# NanoV33.net
KiCad netlist of a schematic drawn in EAGLE
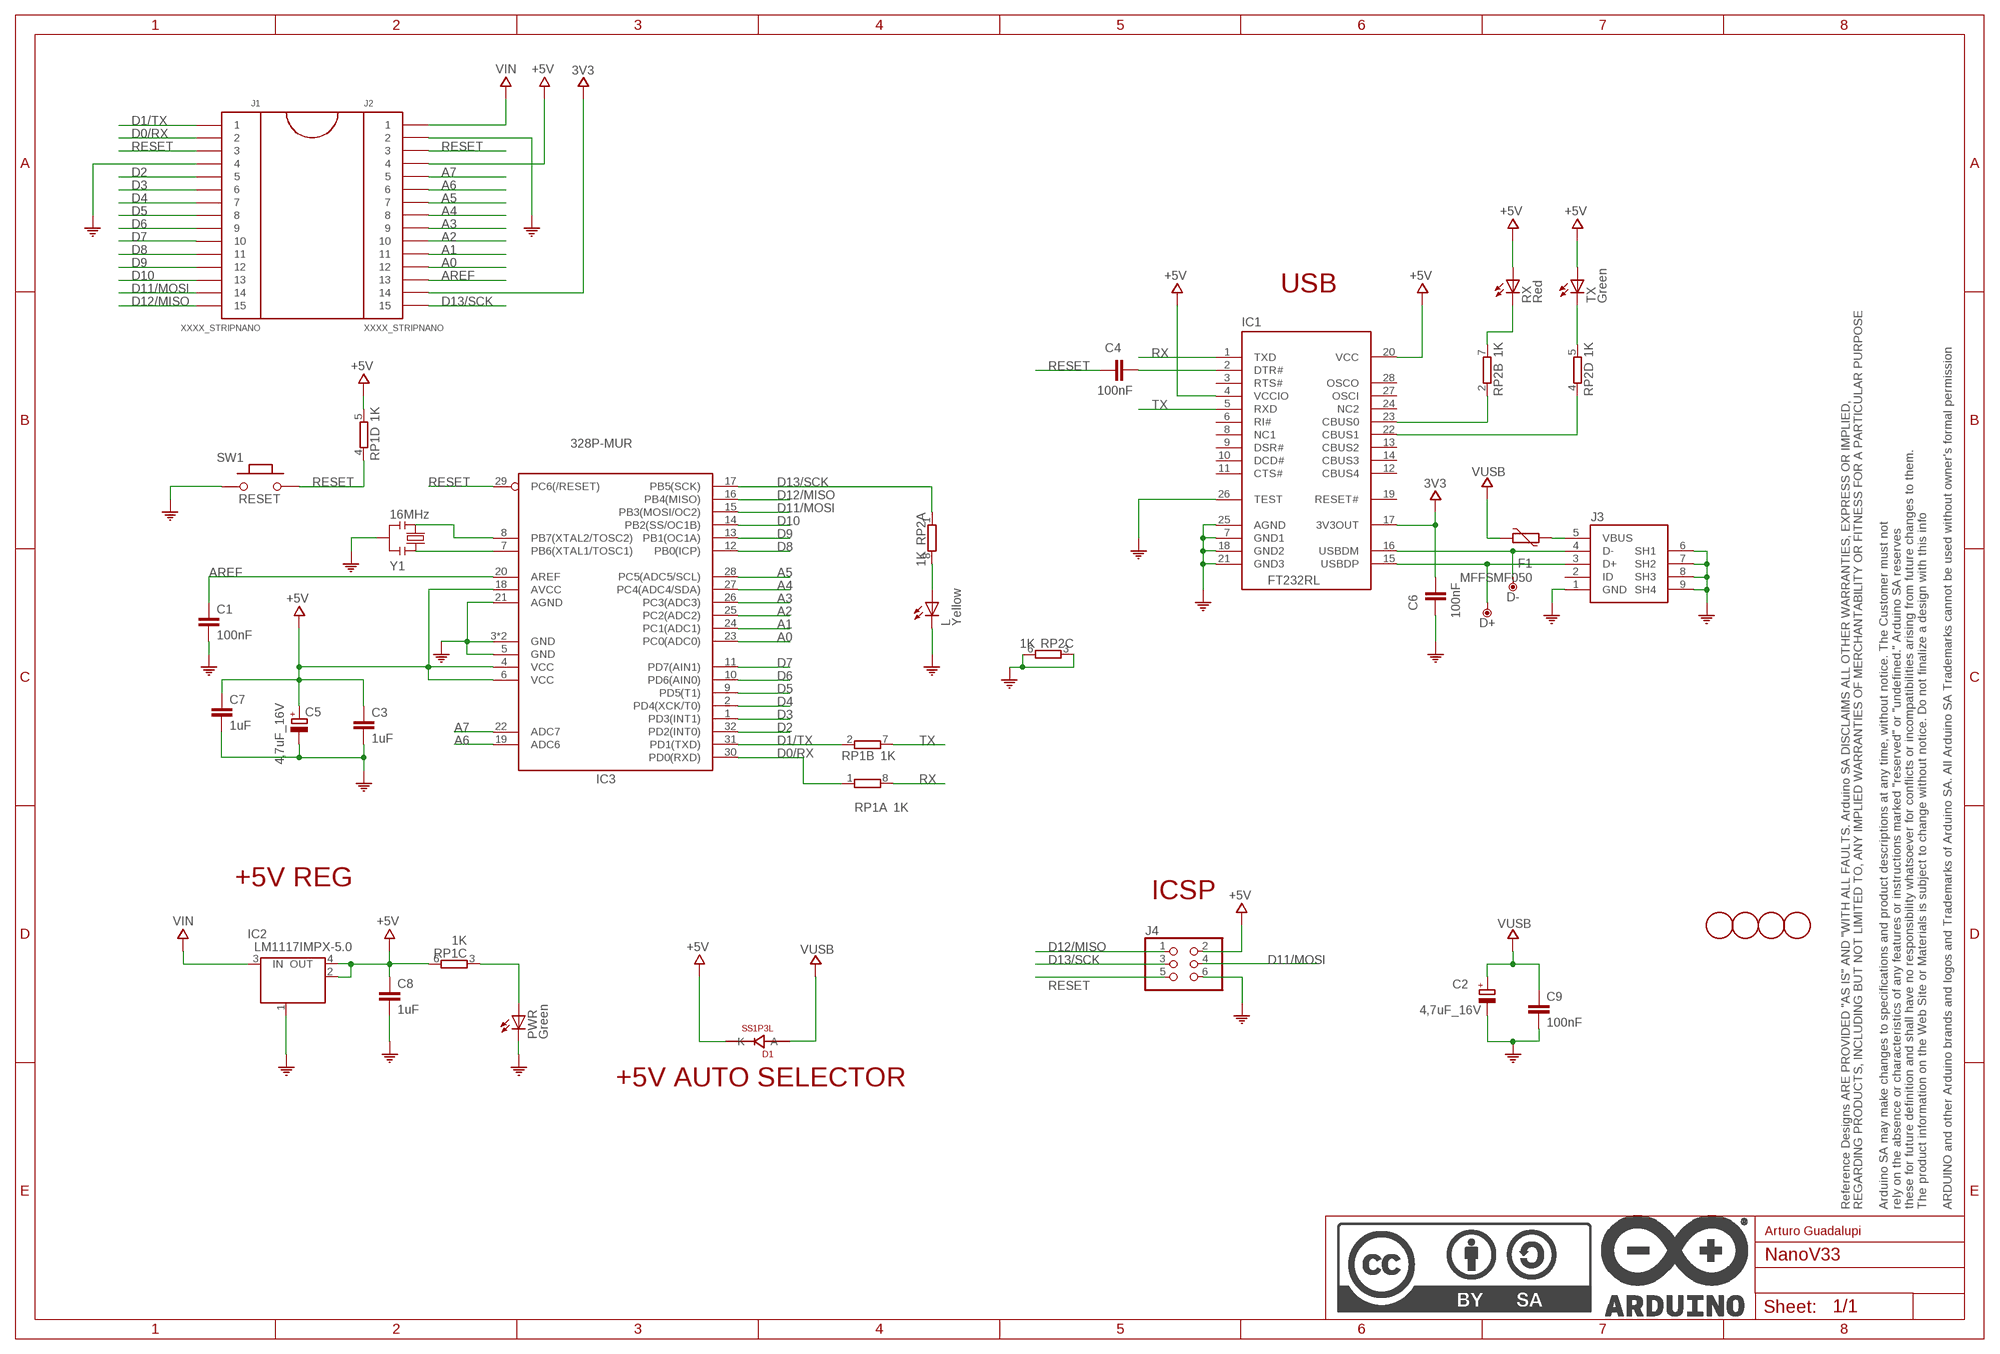
[diagram p0: schematic, sheet 1]

(export (version "E")
  (design (tool "Eeschema 10.0.6"))
  (components
    (comp (ref "C1")
      (value "100nF")
      (footprint "eagle-import:C0603-ROUND")
      (fields (field (name "PART_NUMBER") "cl10b104kbnc"))
      (libsource (lib "eagle-import") (part "0015_100NF_0603"))
    )
    (comp (ref "C2")
      (value "4,7uF_16V")
      (footprint "eagle-import:TAN-A")
      (fields (field (name "PART_NUMBER") "TAJA475MO16RNJ"))
      (libsource (lib "eagle-import") (part "0833_TAJA475MO16RNJ"))
    )
    (comp (ref "C3")
      (value "1uF")
      (footprint "eagle-import:C0603-ROUND")
      (fields (field (name "PART_NUMBER") "1uF_0603/GRM188R61E105KA12D"))
      (libsource (lib "eagle-import") (part "0006_1UF_0603/GRM188R61E105KA12D"))
    )
    (comp (ref "C4")
      (value "100nF")
      (footprint "eagle-import:C0603-ROUND")
      (fields (field (name "PART_NUMBER") "cl10b104kbnc"))
      (libsource (lib "eagle-import") (part "0015_100NF_0603"))
    )
    (comp (ref "C5")
      (value "4,7uF_16V")
      (footprint "eagle-import:TAN-A")
      (fields (field (name "PART_NUMBER") "TAJA475MO16RNJ"))
      (libsource (lib "eagle-import") (part "0833_TAJA475MO16RNJ"))
    )
    (comp (ref "C6")
      (value "100nF")
      (footprint "eagle-import:C0603-ROUND")
      (fields (field (name "PART_NUMBER") "cl10b104kbnc"))
      (libsource (lib "eagle-import") (part "0015_100NF_0603"))
    )
    (comp (ref "C7")
      (value "1uF")
      (footprint "eagle-import:C0603-ROUND")
      (fields (field (name "PART_NUMBER") "1uF_0603/GRM188R61E105KA12D"))
      (libsource (lib "eagle-import") (part "0006_1UF_0603/GRM188R61E105KA12D"))
    )
    (comp (ref "C8")
      (value "1uF")
      (footprint "eagle-import:C0603-ROUND")
      (fields (field (name "PART_NUMBER") "1uF_0603/GRM188R61E105KA12D"))
      (libsource (lib "eagle-import") (part "0006_1UF_0603/GRM188R61E105KA12D"))
    )
    (comp (ref "C9")
      (value "100nF")
      (footprint "eagle-import:C0603-ROUND")
      (fields (field (name "PART_NUMBER") "cl10b104kbnc"))
      (libsource (lib "eagle-import") (part "0015_100NF_0603"))
    )
    (comp (ref "D+")
      (value "DNP")
      (footprint "eagle-import:TP-1.00MM")
      (libsource (lib "eagle-import") (part "TPTP-1.00MM"))
    )
    (comp (ref "D-")
      (value "DNP")
      (footprint "eagle-import:TP-1.00MM")
      (libsource (lib "eagle-import") (part "TPTP-1.00MM"))
    )
    (comp (ref "D1")
      (value "SS1P3L")
      (footprint "eagle-import:DO220AAL")
      (fields (field (name "PART_NUMBER") "SS1P3L-M3/84A"))
      (libsource (lib "eagle-import") (part "0025_SS1P3L-M3/84A"))
    )
    (comp (ref "F1")
      (value "MFFSMF050")
      (footprint "eagle-import:0603-1608X90N")
      (fields (field (name "MANUFACTURER") "Bourns Inc "))
      (libsource (lib "eagle-import") (part "PTC"))
    )
    (comp (ref "FRAME1")
      (value "DNP")
      (footprint "eagle-import:FRAME")
      (libsource (lib "eagle-import") (part "A3-FRAME"))
    )
    (comp (ref "IC1")
      (value "FT232RL")
      (footprint "eagle-import:SSOP28")
      (libsource (lib "eagle-import") (part "0226_FT232RL"))
    )
    (comp (ref "IC2")
      (value "LM1117IMPX-5.0")
      (footprint "eagle-import:LINEAR_SOT223")
      (libsource (lib "eagle-import") (part "0022_LM1117IMPX-5.0"))
    )
    (comp (ref "IC3")
      (value "328P-MUR")
      (footprint "eagle-import:VQFN32")
      (fields (field (name "MANUFACTURER") "ATMEL"))
      (libsource (lib "eagle-import") (part "ATMEGA328P-32MUR"))
    )
    (comp (ref "J1")
      (value "XXXX_STRIPNANO")
      (footprint "eagle-import:HEAD15-NOSS")
      (libsource (lib "eagle-import") (part "XXXX_STRIPNANO"))
    )
    (comp (ref "J2")
      (value "XXXX_STRIPNANO")
      (footprint "eagle-import:HEAD15-NOSS")
      (libsource (lib "eagle-import") (part "XXXX_STRIPNANO"))
    )
    (comp (ref "J3")
      (value "0219_14850")
      (footprint "eagle-import:USB-MINI-B_2")
      (fields (field (name "PART_NUMBER") "14850"))
      (libsource (lib "eagle-import") (part "0219_14850"))
    )
    (comp (ref "J4")
      (value "0114_PH254-203DF118A00V")
      (footprint "eagle-import:2X03")
      (fields (field (name "PART_NUMBER") "PH254-203DF118A00V"))
      (libsource (lib "eagle-import") (part "0114_PH254-203DF118A00V"))
    )
    (comp (ref "L")
      (value "Yellow")
      (footprint "eagle-import:CHIPLED_0805")
      (fields (field (name "PART_NUMBER") "KPT-2012YC"))
      (libsource (lib "eagle-import") (part "0044_KPT-2012YC"))
    )
    (comp (ref "PWR")
      (value "Green")
      (footprint "eagle-import:CHIPLED_0805")
      (fields (field (name "PART_NUMBER") "KPT-2012SGC"))
      (libsource (lib "eagle-import") (part "0043_KPT-2012SGC"))
    )
    (comp (ref "RP1")
      (value "1K")
      (footprint "eagle-import:CAY16")
      (fields (field (name "PART_NUMBER") "064R_1K_/_CAY16-102J4LF"))
      (libsource (lib "eagle-import") (part "0005_064R_1K_/_CAY16-102J4LF"))
    )
    (comp (ref "RP2")
      (value "1K")
      (footprint "eagle-import:CAY16")
      (fields (field (name "PART_NUMBER") "064R_1K_/_CAY16-102J4LF"))
      (libsource (lib "eagle-import") (part "0005_064R_1K_/_CAY16-102J4LF"))
    )
    (comp (ref "RX")
      (value "Red")
      (footprint "eagle-import:CHIPLED_0805")
      (fields (field (name "PART_NUMBER") "KTP-2012SURCK"))
      (libsource (lib "eagle-import") (part "0181_KTP-2012SURCK"))
    )
    (comp (ref "SW1")
      (value "RESET")
      (footprint "eagle-import:SMD_157SW")
      (fields (field (name "PART_NUMBER") "IT-1185AP1C-160G-G_T&R"))
      (libsource (lib "eagle-import") (part "0173_IT-1185AP1C-160G-G_T&R"))
    )
    (comp (ref "TX")
      (value "Green")
      (footprint "eagle-import:CHIPLED_0805")
      (fields (field (name "PART_NUMBER") "KPT-2012SGC"))
      (libsource (lib "eagle-import") (part "0043_KPT-2012SGC"))
    )
    (comp (ref "U$4")
      (value "DNP")
      (footprint "eagle-import:FD-1-1.5")
      (libsource (lib "eagle-import") (part "FIDUCIAL-1.5MM"))
    )
    (comp (ref "U$5")
      (value "DNP")
      (footprint "eagle-import:FD-1-1.5")
      (libsource (lib "eagle-import") (part "FIDUCIAL-1.5MM"))
    )
    (comp (ref "U$53")
      (value "DNP")
      (footprint "eagle-import:FD-1-1.5")
      (libsource (lib "eagle-import") (part "FIDUCIAL-1.5MM"))
    )
    (comp (ref "U$54")
      (value "DNP")
      (footprint "eagle-import:FD-1-1.5")
      (libsource (lib "eagle-import") (part "FIDUCIAL-1.5MM"))
    )
    (comp (ref "Y1")
      (value "16MHz")
      (footprint "eagle-import:RESONATOR")
      (fields (field (name "PART_NUMBER") "CSTCE16M0V53-R0"))
      (libsource (lib "eagle-import") (part "0011_CSTCE16M0V53-R0"))
    )
  )
  (nets
    (net (code "1") (name "+5V") (class "Default")
      (node (ref "C3") (pin "1") (pinfunction "1_1") (pintype "passive"))
      (node (ref "C5") (pin "1") (pinfunction "+_1") (pintype "passive"))
      (node (ref "C7") (pin "1") (pinfunction "1_1") (pintype "passive"))
      (node (ref "C8") (pin "1") (pinfunction "1_1") (pintype "passive"))
      (node (ref "D1") (pin "P$1") (pinfunction "K_P$1") (pintype "bidirectional"))
      (node (ref "IC1") (pin "20") (pinfunction "VCC_20") (pintype "power_in"))
      (node (ref "IC1") (pin "4") (pinfunction "VCCIO_4") (pintype "power_in"))
      (node (ref "IC2") (pin "2") (pinfunction "OUT_2") (pintype "passive"))
      (node (ref "IC2") (pin "4") (pinfunction "OUT_4") (pintype "passive"))
      (node (ref "IC3") (pin "18") (pinfunction "AVCC_18") (pintype "bidirectional"))
      (node (ref "IC3") (pin "4") (pinfunction "VCC_4") (pintype "bidirectional"))
      (node (ref "IC3") (pin "6") (pinfunction "VCC_6") (pintype "bidirectional"))
      (node (ref "J2") (pin "4") (pinfunction "4_4") (pintype "passive"))
      (node (ref "J4") (pin "2") (pinfunction "2_2") (pintype "passive"))
      (node (ref "RP1") (pin "5") (pinfunction "2_5") (pintype "passive"))
      (node (ref "RP1") (pin "6") (pinfunction "2_6") (pintype "passive"))
      (node (ref "RX") (pin "A") (pinfunction "A_A") (pintype "passive"))
      (node (ref "TX") (pin "A") (pinfunction "A_A") (pintype "passive"))
    )
    (net (code "2") (name "/A0") (class "Default")
      (node (ref "IC3") (pin "23") (pinfunction "PC0(ADC0)_23") (pintype "bidirectional"))
      (node (ref "J2") (pin "12") (pinfunction "12_12") (pintype "passive"))
    )
    (net (code "3") (name "/A1") (class "Default")
      (node (ref "IC3") (pin "24") (pinfunction "PC1(ADC1)_24") (pintype "bidirectional"))
      (node (ref "J2") (pin "11") (pinfunction "11_11") (pintype "passive"))
    )
    (net (code "4") (name "/A2") (class "Default")
      (node (ref "IC3") (pin "25") (pinfunction "PC2(ADC2)_25") (pintype "bidirectional"))
      (node (ref "J2") (pin "10") (pinfunction "10_10") (pintype "passive"))
    )
    (net (code "5") (name "/A3") (class "Default")
      (node (ref "IC3") (pin "26") (pinfunction "PC3(ADC3)_26") (pintype "bidirectional"))
      (node (ref "J2") (pin "9") (pinfunction "9_9") (pintype "passive"))
    )
    (net (code "6") (name "/A4") (class "Default")
      (node (ref "IC3") (pin "27") (pinfunction "PC4(ADC4/SDA)_27") (pintype "bidirectional"))
      (node (ref "J2") (pin "8") (pinfunction "8_8") (pintype "passive"))
    )
    (net (code "7") (name "/A5") (class "Default")
      (node (ref "IC3") (pin "28") (pinfunction "PC5(ADC5/SCL)_28") (pintype "bidirectional"))
      (node (ref "J2") (pin "7") (pinfunction "7_7") (pintype "passive"))
    )
    (net (code "8") (name "/A6") (class "Default")
      (node (ref "IC3") (pin "19") (pinfunction "ADC6_19") (pintype "bidirectional"))
      (node (ref "J2") (pin "6") (pinfunction "6_6") (pintype "passive"))
    )
    (net (code "9") (name "/A7") (class "Default")
      (node (ref "IC3") (pin "22") (pinfunction "ADC7_22") (pintype "bidirectional"))
      (node (ref "J2") (pin "5") (pinfunction "5_5") (pintype "passive"))
    )
    (net (code "10") (name "/AREF") (class "Default")
      (node (ref "C1") (pin "1") (pinfunction "1_1") (pintype "passive"))
      (node (ref "IC3") (pin "20") (pinfunction "AREF_20") (pintype "bidirectional"))
      (node (ref "J2") (pin "13") (pinfunction "13_13") (pintype "passive"))
    )
    (net (code "11") (name "/D0{slash}RX") (class "Default")
      (node (ref "IC3") (pin "30") (pinfunction "PD0(RXD)_30") (pintype "bidirectional"))
      (node (ref "J1") (pin "2") (pinfunction "2_2") (pintype "passive"))
      (node (ref "RP1") (pin "1") (pinfunction "1_1") (pintype "passive"))
    )
    (net (code "12") (name "/D1{slash}TX") (class "Default")
      (node (ref "IC3") (pin "31") (pinfunction "PD1(TXD)_31") (pintype "bidirectional"))
      (node (ref "J1") (pin "1") (pinfunction "1_1") (pintype "passive"))
      (node (ref "RP1") (pin "2") (pinfunction "1_2") (pintype "passive"))
    )
    (net (code "13") (name "/D2") (class "Default")
      (node (ref "IC3") (pin "32") (pinfunction "PD2(INT0)_32") (pintype "bidirectional"))
      (node (ref "J1") (pin "5") (pinfunction "5_5") (pintype "passive"))
    )
    (net (code "14") (name "/D3") (class "Default")
      (node (ref "IC3") (pin "1") (pinfunction "PD3(INT1)_1") (pintype "bidirectional"))
      (node (ref "J1") (pin "6") (pinfunction "6_6") (pintype "passive"))
    )
    (net (code "15") (name "/D4") (class "Default")
      (node (ref "IC3") (pin "2") (pinfunction "PD4(XCK/T0)_2") (pintype "bidirectional"))
      (node (ref "J1") (pin "7") (pinfunction "7_7") (pintype "passive"))
    )
    (net (code "16") (name "/D5") (class "Default")
      (node (ref "IC3") (pin "9") (pinfunction "PD5(T1)_9") (pintype "bidirectional"))
      (node (ref "J1") (pin "8") (pinfunction "8_8") (pintype "passive"))
    )
    (net (code "17") (name "/D6") (class "Default")
      (node (ref "IC3") (pin "10") (pinfunction "PD6(AIN0)_10") (pintype "bidirectional"))
      (node (ref "J1") (pin "9") (pinfunction "9_9") (pintype "passive"))
    )
    (net (code "18") (name "/D7") (class "Default")
      (node (ref "IC3") (pin "11") (pinfunction "PD7(AIN1)_11") (pintype "bidirectional"))
      (node (ref "J1") (pin "10") (pinfunction "10_10") (pintype "passive"))
    )
    (net (code "19") (name "/D8") (class "Default")
      (node (ref "IC3") (pin "12") (pinfunction "PB0(ICP)_12") (pintype "bidirectional"))
      (node (ref "J1") (pin "11") (pinfunction "11_11") (pintype "passive"))
    )
    (net (code "20") (name "/D9") (class "Default")
      (node (ref "IC3") (pin "13") (pinfunction "PB1(OC1A)_13") (pintype "bidirectional"))
      (node (ref "J1") (pin "12") (pinfunction "12_12") (pintype "passive"))
    )
    (net (code "21") (name "/D10") (class "Default")
      (node (ref "IC3") (pin "14") (pinfunction "PB2(SS/OC1B)_14") (pintype "bidirectional"))
      (node (ref "J1") (pin "13") (pinfunction "13_13") (pintype "passive"))
    )
    (net (code "22") (name "/D11{slash}MOSI") (class "Default")
      (node (ref "IC3") (pin "15") (pinfunction "PB3(MOSI/OC2)_15") (pintype "bidirectional"))
      (node (ref "J1") (pin "14") (pinfunction "14_14") (pintype "passive"))
      (node (ref "J4") (pin "4") (pinfunction "4_4") (pintype "passive"))
    )
    (net (code "23") (name "/D12{slash}MISO") (class "Default")
      (node (ref "IC3") (pin "16") (pinfunction "PB4(MISO)_16") (pintype "bidirectional"))
      (node (ref "J1") (pin "15") (pinfunction "15_15") (pintype "passive"))
      (node (ref "J4") (pin "1") (pinfunction "1_1") (pintype "passive"))
    )
    (net (code "24") (name "/D13{slash}SCK") (class "Default")
      (node (ref "IC3") (pin "17") (pinfunction "PB5(SCK)_17") (pintype "bidirectional"))
      (node (ref "J2") (pin "15") (pinfunction "15_15") (pintype "passive"))
      (node (ref "J4") (pin "3") (pinfunction "3_3") (pintype "passive"))
      (node (ref "RP2") (pin "1") (pinfunction "1_1") (pintype "passive"))
    )
    (net (code "25") (name "/RESET") (class "Default")
      (node (ref "C4") (pin "1") (pinfunction "1_1") (pintype "passive"))
      (node (ref "IC3") (pin "29") (pinfunction "PC6(/RESET)_29") (pintype "bidirectional"))
      (node (ref "J1") (pin "3") (pinfunction "3_3") (pintype "passive"))
      (node (ref "J2") (pin "3") (pinfunction "3_3") (pintype "passive"))
      (node (ref "J4") (pin "5") (pinfunction "5_5") (pintype "passive"))
      (node (ref "RP1") (pin "4") (pinfunction "1_4") (pintype "passive"))
      (node (ref "SW1") (pin "2") (pinfunction "2_2") (pintype "passive"))
    )
    (net (code "26") (name "/RX") (class "Default")
      (node (ref "IC1") (pin "1") (pinfunction "TXD_1") (pintype "output"))
      (node (ref "RP1") (pin "8") (pinfunction "2_8") (pintype "passive"))
    )
    (net (code "27") (name "/TX") (class "Default")
      (node (ref "IC1") (pin "5") (pinfunction "RXD_5") (pintype "input"))
      (node (ref "RP1") (pin "7") (pinfunction "2_7") (pintype "passive"))
    )
    (net (code "28") (name "3V3") (class "Default")
      (node (ref "C6") (pin "2") (pinfunction "2_2") (pintype "passive"))
      (node (ref "IC1") (pin "17") (pinfunction "3V3OUT_17") (pintype "power_in"))
      (node (ref "J2") (pin "14") (pinfunction "14_14") (pintype "passive"))
    )
    (net (code "29") (name "COM") (class "Default")
      (node (ref "C1") (pin "2") (pinfunction "2_2") (pintype "passive"))
      (node (ref "C2") (pin "2") (pinfunction "-_2") (pintype "passive"))
      (node (ref "C3") (pin "2") (pinfunction "2_2") (pintype "passive"))
      (node (ref "C5") (pin "2") (pinfunction "-_2") (pintype "passive"))
      (node (ref "C6") (pin "1") (pinfunction "1_1") (pintype "passive"))
      (node (ref "C7") (pin "2") (pinfunction "2_2") (pintype "passive"))
      (node (ref "C8") (pin "2") (pinfunction "2_2") (pintype "passive"))
      (node (ref "C9") (pin "2") (pinfunction "2_2") (pintype "passive"))
      (node (ref "IC1") (pin "18") (pinfunction "GND2_18") (pintype "power_in"))
      (node (ref "IC1") (pin "21") (pinfunction "GND3_21") (pintype "power_in"))
      (node (ref "IC1") (pin "25") (pinfunction "AGND_25") (pintype "power_in"))
      (node (ref "IC1") (pin "26") (pinfunction "TEST_26") (pintype "bidirectional"))
      (node (ref "IC1") (pin "7") (pinfunction "GND1_7") (pintype "power_in"))
      (node (ref "IC2") (pin "1") (pinfunction "GND/ADJ_1") (pintype "input"))
      (node (ref "IC3") (pin "21") (pinfunction "AGND_21") (pintype "bidirectional"))
      (node (ref "IC3") (pin "3") (pinfunction "GND_3") (pintype "bidirectional"))
      (node (ref "IC3") (pin "33") (pinfunction "GND_33") (pintype "bidirectional"))
      (node (ref "IC3") (pin "5") (pinfunction "GND_5") (pintype "bidirectional"))
      (node (ref "J1") (pin "4") (pinfunction "4_4") (pintype "passive"))
      (node (ref "J2") (pin "2") (pinfunction "2_2") (pintype "passive"))
      (node (ref "J3") (pin "1") (pinfunction "GND_1") (pintype "passive"))
      (node (ref "J3") (pin "6") (pinfunction "SH1_6") (pintype "passive"))
      (node (ref "J3") (pin "7") (pinfunction "SH2_7") (pintype "passive"))
      (node (ref "J3") (pin "8") (pinfunction "SH3_8") (pintype "passive"))
      (node (ref "J3") (pin "9") (pinfunction "SH4_9") (pintype "passive"))
      (node (ref "J4") (pin "6") (pinfunction "6_6") (pintype "passive"))
      (node (ref "L") (pin "C") (pinfunction "C_C") (pintype "passive"))
      (node (ref "PWR") (pin "C") (pinfunction "C_C") (pintype "passive"))
      (node (ref "RP2") (pin "3") (pinfunction "1_3") (pintype "passive"))
      (node (ref "RP2") (pin "6") (pinfunction "2_6") (pintype "passive"))
      (node (ref "SW1") (pin "1") (pinfunction "1_1") (pintype "passive"))
      (node (ref "Y1") (pin "2") (pinfunction "2_2") (pintype "passive"))
    )
    (net (code "30") (name "Net-(D+-P$1)") (class "Default")
      (node (ref "D+") (pin "X") (pinfunction "P$1_X") (pintype "passive"))
      (node (ref "IC1") (pin "15") (pinfunction "USBDP_15") (pintype "bidirectional"))
      (node (ref "J3") (pin "3") (pinfunction "D+_3") (pintype "bidirectional"))
    )
    (net (code "31") (name "Net-(D--P$1)") (class "Default")
      (node (ref "D-") (pin "X") (pinfunction "P$1_X") (pintype "passive"))
      (node (ref "IC1") (pin "16") (pinfunction "USBDM_16") (pintype "bidirectional"))
      (node (ref "J3") (pin "4") (pinfunction "D-_4") (pintype "bidirectional"))
    )
    (net (code "32") (name "Net-(IC1-CBUS0)") (class "Default")
      (node (ref "IC1") (pin "23") (pinfunction "CBUS0_23") (pintype "bidirectional"))
      (node (ref "RP2") (pin "2") (pinfunction "1_2") (pintype "passive"))
    )
    (net (code "33") (name "Net-(IC1-CBUS1)") (class "Default")
      (node (ref "IC1") (pin "22") (pinfunction "CBUS1_22") (pintype "bidirectional"))
      (node (ref "RP2") (pin "4") (pinfunction "1_4") (pintype "passive"))
    )
    (net (code "34") (name "Net-(IC1-DTR#)") (class "Default")
      (node (ref "C4") (pin "2") (pinfunction "2_2") (pintype "passive"))
      (node (ref "IC1") (pin "2") (pinfunction "DTR#_2") (pintype "output"))
    )
    (net (code "35") (name "Net-(IC3-PB6(XTAL1{slash}TOSC1))") (class "Default")
      (node (ref "IC3") (pin "7") (pinfunction "PB6(XTAL1/TOSC1)_7") (pintype "bidirectional"))
      (node (ref "Y1") (pin "1") (pinfunction "1_1") (pintype "passive"))
    )
    (net (code "36") (name "Net-(IC3-PB7(XTAL2{slash}TOSC2))") (class "Default")
      (node (ref "IC3") (pin "8") (pinfunction "PB7(XTAL2/TOSC2)_8") (pintype "bidirectional"))
      (node (ref "Y1") (pin "3") (pinfunction "3_3") (pintype "passive"))
    )
    (net (code "37") (name "Net-(J3-VBUS)") (class "Default")
      (node (ref "F1") (pin "2") (pinfunction "2_2") (pintype "passive"))
      (node (ref "J3") (pin "5") (pinfunction "VBUS_5") (pintype "power_in"))
    )
    (net (code "38") (name "Net-(RP1C-1)") (class "Default")
      (node (ref "PWR") (pin "A") (pinfunction "A_A") (pintype "passive"))
      (node (ref "RP1") (pin "3") (pinfunction "1_3") (pintype "passive"))
    )
    (net (code "39") (name "Net-(RP2A-2)") (class "Default")
      (node (ref "L") (pin "A") (pinfunction "A_A") (pintype "passive"))
      (node (ref "RP2") (pin "8") (pinfunction "2_8") (pintype "passive"))
    )
    (net (code "40") (name "Net-(RP2B-2)") (class "Default")
      (node (ref "RP2") (pin "7") (pinfunction "2_7") (pintype "passive"))
      (node (ref "RX") (pin "C") (pinfunction "C_C") (pintype "passive"))
    )
    (net (code "41") (name "Net-(RP2D-2)") (class "Default")
      (node (ref "RP2") (pin "5") (pinfunction "2_5") (pintype "passive"))
      (node (ref "TX") (pin "C") (pinfunction "C_C") (pintype "passive"))
    )
    (net (code "42") (name "VIN") (class "Default")
      (node (ref "IC2") (pin "3") (pinfunction "IN_3") (pintype "input"))
      (node (ref "J2") (pin "1") (pinfunction "1_1") (pintype "passive"))
    )
    (net (code "43") (name "VUSB") (class "Default")
      (node (ref "C2") (pin "1") (pinfunction "+_1") (pintype "passive"))
      (node (ref "C9") (pin "1") (pinfunction "1_1") (pintype "passive"))
      (node (ref "D1") (pin "P$2") (pinfunction "A_P$2") (pintype "bidirectional"))
      (node (ref "F1") (pin "1") (pinfunction "1_1") (pintype "passive"))
    )
    (net (code "44") (name "unconnected-(IC1-CBUS2-Pad13)") (class "Default")
      (node (ref "IC1") (pin "13") (pinfunction "CBUS2_13") (pintype "bidirectional"))
    )
    (net (code "45") (name "unconnected-(IC1-CBUS3-Pad14)") (class "Default")
      (node (ref "IC1") (pin "14") (pinfunction "CBUS3_14") (pintype "bidirectional"))
    )
    (net (code "46") (name "unconnected-(IC1-CBUS4-Pad12)") (class "Default")
      (node (ref "IC1") (pin "12") (pinfunction "CBUS4_12") (pintype "bidirectional"))
    )
    (net (code "47") (name "unconnected-(IC1-CTS#-Pad11)") (class "Default")
      (node (ref "IC1") (pin "11") (pinfunction "CTS#_11") (pintype "bidirectional"))
    )
    (net (code "48") (name "unconnected-(IC1-DCD#-Pad10)") (class "Default")
      (node (ref "IC1") (pin "10") (pinfunction "DCD#_10") (pintype "bidirectional"))
    )
    (net (code "49") (name "unconnected-(IC1-DSR#-Pad9)") (class "Default")
      (node (ref "IC1") (pin "9") (pinfunction "DSR#_9") (pintype "bidirectional"))
    )
    (net (code "50") (name "unconnected-(IC1-NC1-Pad8)") (class "Default")
      (node (ref "IC1") (pin "8") (pinfunction "NC1_8") (pintype "bidirectional"))
    )
    (net (code "51") (name "unconnected-(IC1-NC2-Pad24)") (class "Default")
      (node (ref "IC1") (pin "24") (pinfunction "NC2_24") (pintype "no_connect"))
    )
    (net (code "52") (name "unconnected-(IC1-OSCI-Pad27)") (class "Default")
      (node (ref "IC1") (pin "27") (pinfunction "OSCI_27") (pintype "bidirectional"))
    )
    (net (code "53") (name "unconnected-(IC1-OSCO-Pad28)") (class "Default")
      (node (ref "IC1") (pin "28") (pinfunction "OSCO_28") (pintype "output"))
    )
    (net (code "54") (name "unconnected-(IC1-RESET#-Pad19)") (class "Default")
      (node (ref "IC1") (pin "19") (pinfunction "RESET#_19") (pintype "bidirectional"))
    )
    (net (code "55") (name "unconnected-(IC1-RI#-Pad6)") (class "Default")
      (node (ref "IC1") (pin "6") (pinfunction "RI#_6") (pintype "bidirectional"))
    )
    (net (code "56") (name "unconnected-(IC1-RTS#-Pad3)") (class "Default")
      (node (ref "IC1") (pin "3") (pinfunction "RTS#_3") (pintype "output"))
    )
    (net (code "57") (name "unconnected-(J3-ID-Pad2)") (class "Default")
      (node (ref "J3") (pin "2") (pinfunction "ID_2") (pintype "bidirectional"))
    )
  )
)
